# GCIT_1_0.net
KiCad netlist of a schematic drawn in Altium Designer
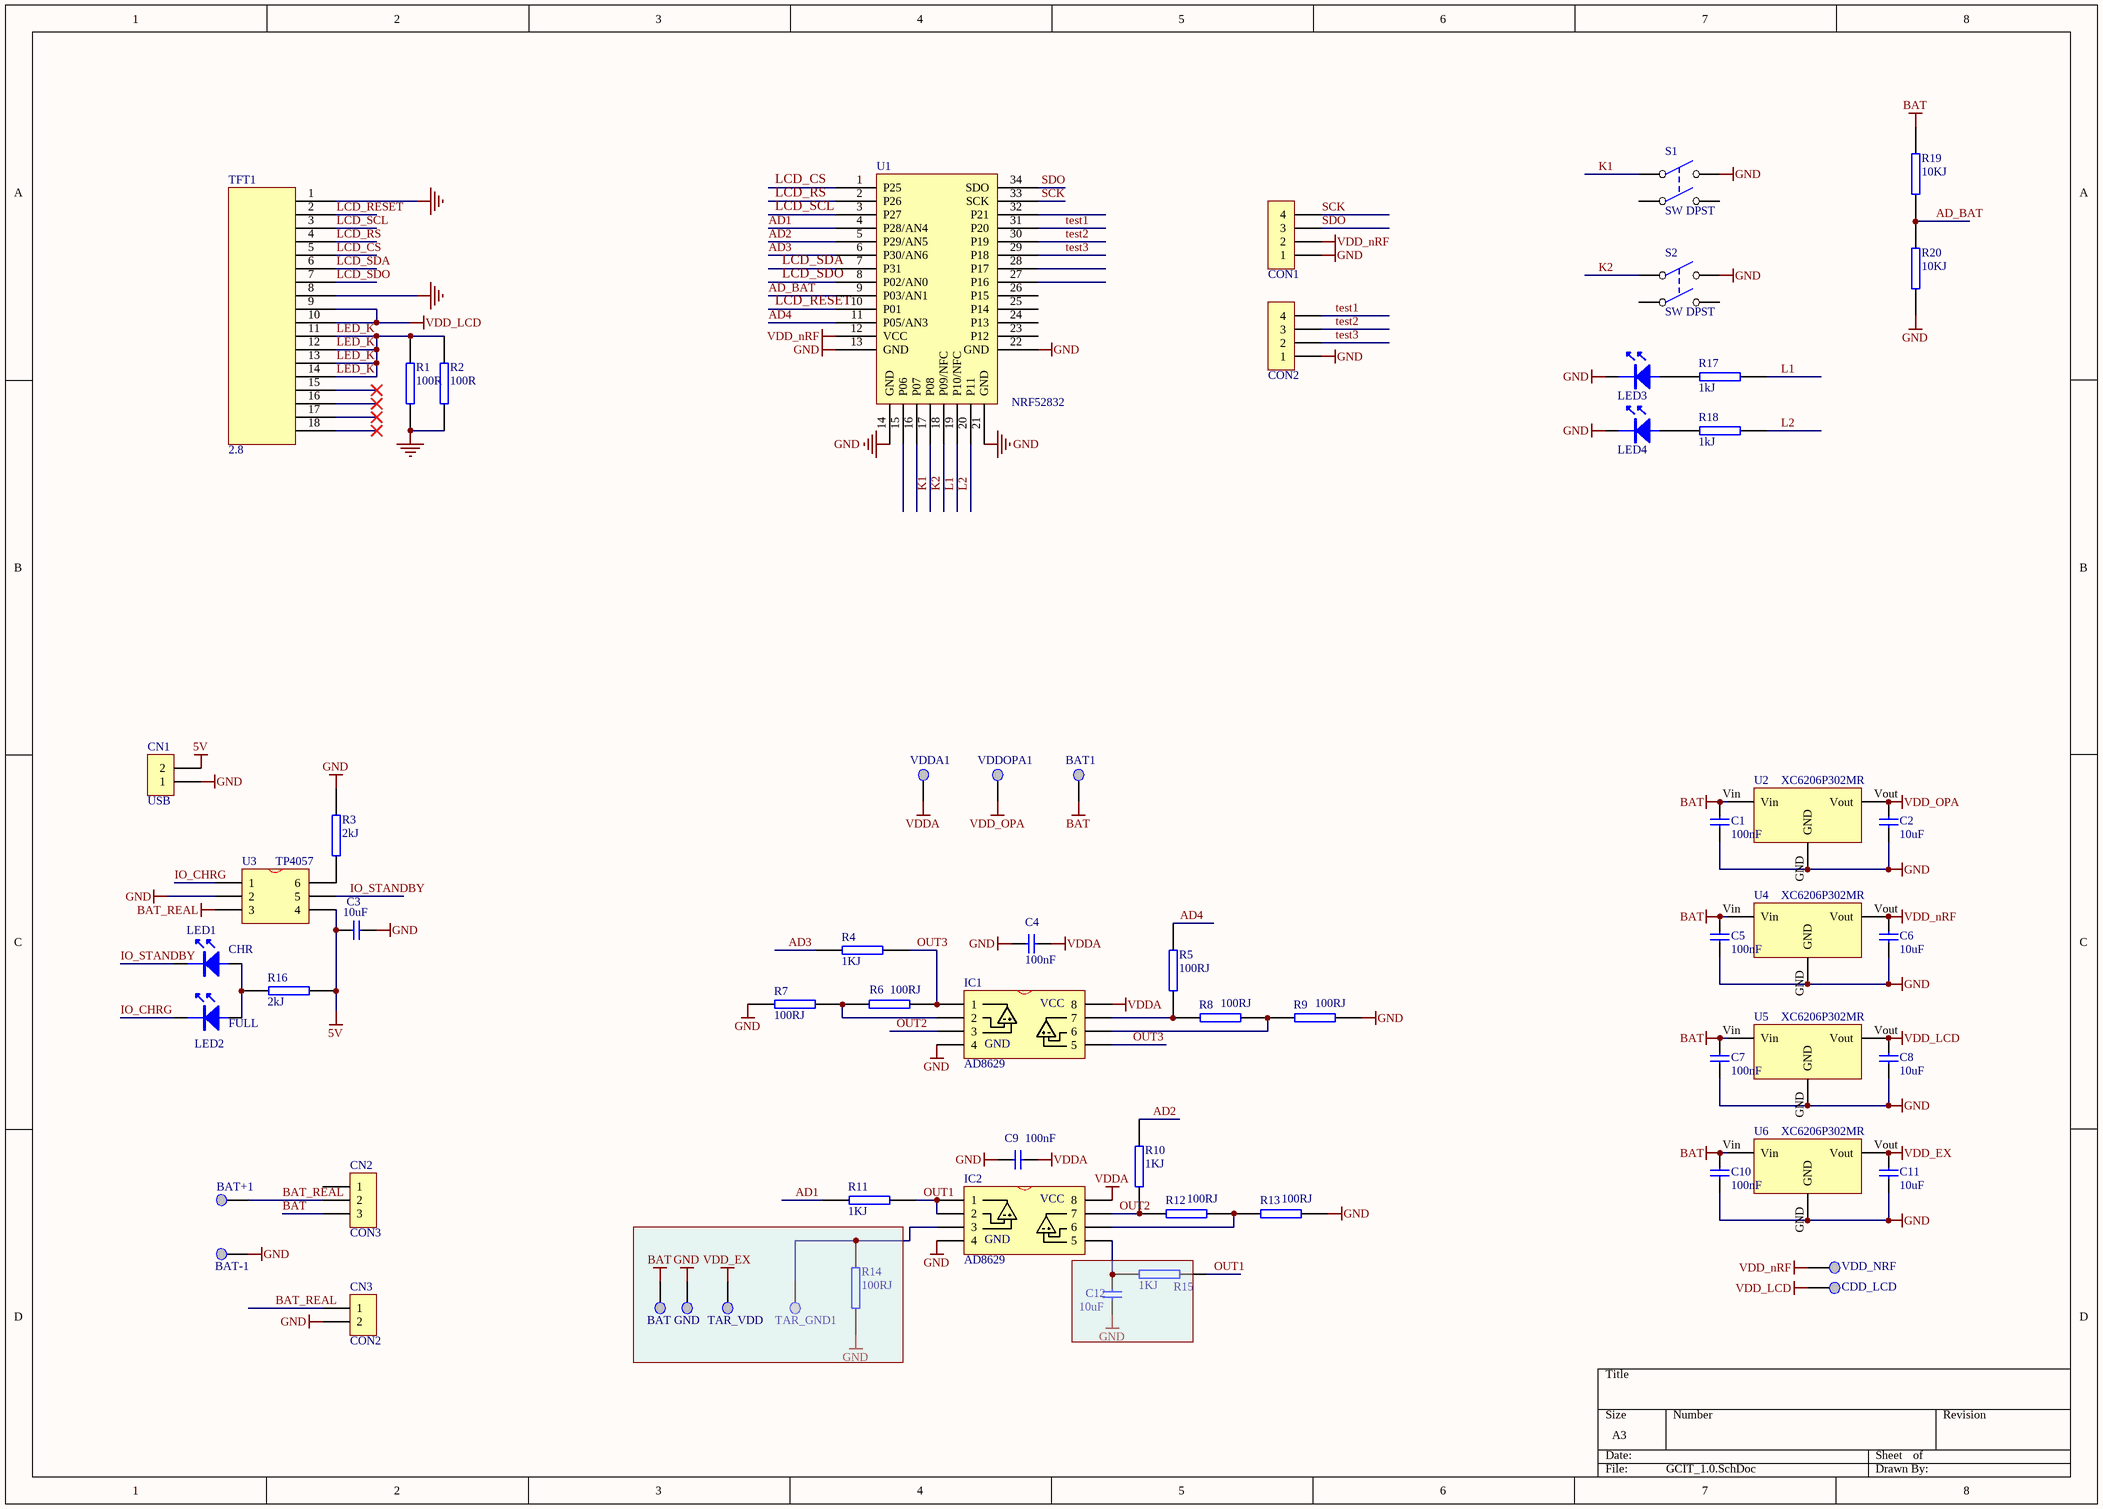
[diagram p0: GCIT_1.0.SchDoc]

(export (version "E")
  (design (tool "Eeschema 10.0.6"))
  (components
    (comp (ref "BAT") (value "~") (footprint "BAT_PAD") (libsource (lib "LZMSCH库") (part "PAD")))
    (comp (ref "BAT+1") (value "~") (footprint "BAT_PAD") (libsource (lib "LZMSCH库") (part "PAD")))
    (comp (ref "BAT-1") (value "~") (footprint "BAT_PAD") (libsource (lib "LZMSCH库") (part "PAD")))
    (comp (ref "BAT1") (value "~") (footprint "BAT_PAD") (libsource (lib "LZMSCH库") (part "PAD")))
    (comp (ref "C1")
      (value "100nF")
      (footprint "0603C")
      (description "Capacitor, X7R, ?0%")
      (fields (field (name "PART NUMBER") "C0402-47n") (field (name "PUBLISHER") "Nordic Semiconductor"))
      (libsource (lib "Nordic Passive DB") (part "CAP"))
    )
    (comp (ref "C2")
      (value "10uF")
      (footprint "0603C")
      (description "Capacitor, X7R, ?0%")
      (fields (field (name "PART NUMBER") "C0402-47n") (field (name "PUBLISHER") "Nordic Semiconductor"))
      (libsource (lib "Nordic Passive DB") (part "CAP"))
    )
    (comp (ref "C3")
      (value "10uF")
      (footprint "0603C")
      (description "Capacitor, X7R, ?0%")
      (fields (field (name "PART NUMBER") "C0402-47n") (field (name "PUBLISHER") "Nordic Semiconductor"))
      (libsource (lib "Nordic Passive DB") (part "CAP"))
    )
    (comp (ref "C4")
      (value "100nF")
      (footprint "0603C")
      (description "Capacitor, X7R, ?0%")
      (fields (field (name "PART NUMBER") "C0402-47n") (field (name "PUBLISHER") "Nordic Semiconductor"))
      (libsource (lib "Nordic Passive DB") (part "CAP"))
    )
    (comp (ref "C5")
      (value "100nF")
      (footprint "0603C")
      (description "Capacitor, X7R, ?0%")
      (fields (field (name "PART NUMBER") "C0402-47n") (field (name "PUBLISHER") "Nordic Semiconductor"))
      (libsource (lib "Nordic Passive DB") (part "CAP"))
    )
    (comp (ref "C6")
      (value "10uF")
      (footprint "0603C")
      (description "Capacitor, X7R, ?0%")
      (fields (field (name "PART NUMBER") "C0402-47n") (field (name "PUBLISHER") "Nordic Semiconductor"))
      (libsource (lib "Nordic Passive DB") (part "CAP"))
    )
    (comp (ref "C7")
      (value "100nF")
      (footprint "0603C")
      (description "Capacitor, X7R, ?0%")
      (fields (field (name "PART NUMBER") "C0402-47n") (field (name "PUBLISHER") "Nordic Semiconductor"))
      (libsource (lib "Nordic Passive DB") (part "CAP"))
    )
    (comp (ref "C8")
      (value "10uF")
      (footprint "0603C")
      (description "Capacitor, X7R, ?0%")
      (fields (field (name "PART NUMBER") "C0402-47n") (field (name "PUBLISHER") "Nordic Semiconductor"))
      (libsource (lib "Nordic Passive DB") (part "CAP"))
    )
    (comp (ref "C9")
      (value "100nF")
      (footprint "0603C")
      (description "Capacitor, X7R, ?0%")
      (fields (field (name "PART NUMBER") "C0402-47n") (field (name "PUBLISHER") "Nordic Semiconductor"))
      (libsource (lib "Nordic Passive DB") (part "CAP"))
    )
    (comp (ref "C10")
      (value "100nF")
      (footprint "0603C")
      (description "Capacitor, X7R, ?0%")
      (fields (field (name "PART NUMBER") "C0402-47n") (field (name "PUBLISHER") "Nordic Semiconductor"))
      (libsource (lib "Nordic Passive DB") (part "CAP"))
    )
    (comp (ref "C11")
      (value "10uF")
      (footprint "0603C")
      (description "Capacitor, X7R, ?0%")
      (fields (field (name "PART NUMBER") "C0402-47n") (field (name "PUBLISHER") "Nordic Semiconductor"))
      (libsource (lib "Nordic Passive DB") (part "CAP"))
    )
    (comp (ref "C12")
      (value "10uF")
      (footprint "0603C")
      (description "Capacitor, X7R, ?0%")
      (fields (field (name "PART NUMBER") "C0402-47n") (field (name "PUBLISHER") "Nordic Semiconductor"))
      (libsource (lib "Nordic Passive DB") (part "CAP"))
    )
    (comp (ref "CDD_LCD") (value "~") (footprint "BAT_PAD") (libsource (lib "LZMSCH库") (part "PAD")))
    (comp (ref "CN1")
      (value "USB")
      (footprint "USB")
      (description "Connector")
      (libsource (lib "") (part "CON2_1"))
    )
    (comp (ref "CN2")
      (value "CON3")
      (footprint "MSK-12C01-07")
      (description "Connector")
      (libsource (lib "LZMSCH库") (part "CON3"))
    )
    (comp (ref "CN3")
      (value "CON2")
      (footprint "SIP-2P")
      (description "Connector")
      (libsource (lib "LZMSCH库") (part "CON2"))
    )
    (comp (ref "CON1")
      (value "CON4")
      (footprint "SIP-4P")
      (description "Connector")
      (libsource (lib "LZMSCH库") (part "CON4"))
    )
    (comp (ref "CON2")
      (value "CON4")
      (footprint "SIP-4P")
      (description "Connector")
      (libsource (lib "LZMSCH库") (part "CON4"))
    )
    (comp (ref "GND") (value "~") (footprint "BAT_PAD") (libsource (lib "LZMSCH库") (part "PAD")))
    (comp (ref "IC1") (value "AD8629") (footprint "SO-8") (libsource (lib "") (part "LM358_1")))
    (comp (ref "IC2") (value "AD8629") (footprint "SO-8") (libsource (lib "LZMSCH库") (part "LM358")))
    (comp (ref "LED1") (value "CHR") (footprint "0603LED") (libsource (lib "LZMSCH库") (part "LED")))
    (comp (ref "LED2") (value "FULL") (footprint "0603LED") (libsource (lib "LZMSCH库") (part "LED")))
    (comp (ref "LED3") (value "CHR") (footprint "0603LED") (libsource (lib "LZMSCH库") (part "LED")))
    (comp (ref "LED4") (value "[]") (footprint "0603LED") (libsource (lib "LZMSCH库") (part "LED")))
    (comp (ref "R1") (value "100R") (footprint "0603R") (libsource (lib "*") (part "RES2")))
    (comp (ref "R2") (value "100R") (footprint "0603R") (libsource (lib "*") (part "RES2")))
    (comp (ref "R3") (value "2kJ") (footprint "0603R") (libsource (lib "*") (part "RES2")))
    (comp (ref "R4") (value "1KJ") (footprint "0603R") (libsource (lib "*") (part "RES2")))
    (comp (ref "R5") (value "100RJ") (footprint "0603R") (libsource (lib "*") (part "RES2")))
    (comp (ref "R6") (value "100RJ") (footprint "0603R") (libsource (lib "*") (part "RES2")))
    (comp (ref "R7") (value "100RJ") (footprint "0603R") (libsource (lib "*") (part "RES2")))
    (comp (ref "R8") (value "100RJ") (footprint "0603R") (libsource (lib "*") (part "RES2")))
    (comp (ref "R9") (value "100RJ") (footprint "0603R") (libsource (lib "*") (part "RES2")))
    (comp (ref "R10") (value "1KJ") (footprint "0603R") (libsource (lib "*") (part "RES2")))
    (comp (ref "R11") (value "1KJ") (footprint "0603R") (libsource (lib "*") (part "RES2")))
    (comp (ref "R12") (value "100RJ") (footprint "0603R") (libsource (lib "*") (part "RES2")))
    (comp (ref "R13") (value "100RJ") (footprint "0603R") (libsource (lib "*") (part "RES2")))
    (comp (ref "R14") (value "100RJ") (footprint "0603R") (libsource (lib "*") (part "RES2")))
    (comp (ref "R15") (value "1KJ") (footprint "0603R") (libsource (lib "*") (part "RES2")))
    (comp (ref "R16") (value "2kJ") (footprint "0603R") (libsource (lib "*") (part "RES2")))
    (comp (ref "R17") (value "1kJ") (footprint "0603R") (libsource (lib "*") (part "RES2")))
    (comp (ref "R18") (value "1kJ") (footprint "0603R") (libsource (lib "*") (part "RES2")))
    (comp (ref "R19") (value "10KJ") (footprint "0603R") (libsource (lib "*") (part "RES2")))
    (comp (ref "R20") (value "10KJ") (footprint "0603R") (libsource (lib "*") (part "RES2")))
    (comp (ref "S1") (value "SW DPST") (footprint "key4x4") (libsource (lib "LZMSCH库") (part "SW DPST")))
    (comp (ref "S2") (value "SW DPST") (footprint "key4x4") (libsource (lib "LZMSCH库") (part "SW DPST")))
    (comp (ref "TAR_GND1") (value "~") (footprint "DEBUG_PAD") (libsource (lib "LZMSCH库") (part "PAD")))
    (comp (ref "TAR_VDD") (value "~") (footprint "BAT_PAD") (libsource (lib "LZMSCH库") (part "PAD")))
    (comp (ref "TFT1") (value "2.8") (footprint "TFT2.8-ZHA") (libsource (lib "*") (part "18P")))
    (comp (ref "U1")
      (value "NRF52832")
      (footprint "NRF52832_MODEL")
      (libsource (lib "LZMSCH库") (part "NRF52832"))
    )
    (comp (ref "U2")
      (value "XC6206P302MR")
      (footprint "SOT-23-S-LDO")
      (libsource (lib "LZMSCH库") (part "7805"))
    )
    (comp (ref "U3") (value "TP4057") (footprint "SOT23-6-SMALL") (libsource (lib "LZMSCH库") (part "DIP6")))
    (comp (ref "U4")
      (value "XC6206P302MR")
      (footprint "SOT-23-S-LDO")
      (libsource (lib "LZMSCH库") (part "7805"))
    )
    (comp (ref "U5")
      (value "XC6206P302MR")
      (footprint "SOT-23-S-LDO")
      (libsource (lib "LZMSCH库") (part "7805"))
    )
    (comp (ref "U6")
      (value "XC6206P302MR")
      (footprint "SOT-23-S-LDO")
      (libsource (lib "LZMSCH库") (part "7805"))
    )
    (comp (ref "VDDA1") (value "~") (footprint "BAT_PAD") (libsource (lib "LZMSCH库") (part "PAD")))
    (comp (ref "VDDOPA1") (value "~") (footprint "BAT_PAD") (libsource (lib "LZMSCH库") (part "PAD")))
    (comp (ref "VDD_NRF") (value "~") (footprint "BAT_PAD") (libsource (lib "LZMSCH库") (part "PAD")))
  )
  (nets
    (net (code "1") (name "/AD1") (class "Default")
      (node (ref "R11") (pin "2") (pinfunction "2_2") (pintype "passive"))
      (node (ref "U1") (pin "4") (pinfunction "P28/AN4_4") (pintype "passive"))
    )
    (net (code "2") (name "/AD2") (class "Default")
      (node (ref "R10") (pin "2") (pinfunction "2_2") (pintype "passive"))
      (node (ref "U1") (pin "5") (pinfunction "P29/AN5_5") (pintype "passive"))
    )
    (net (code "3") (name "/AD3") (class "Default")
      (node (ref "R4") (pin "2") (pinfunction "2_2") (pintype "passive"))
      (node (ref "U1") (pin "6") (pinfunction "P30/AN6_6") (pintype "passive"))
    )
    (net (code "4") (name "/AD4") (class "Default")
      (node (ref "R5") (pin "2") (pinfunction "2_2") (pintype "passive"))
      (node (ref "U1") (pin "11") (pinfunction "P05/AN3_11") (pintype "passive"))
    )
    (net (code "5") (name "/AD_BAT") (class "Default")
      (node (ref "R19") (pin "1") (pinfunction "1_1") (pintype "passive"))
      (node (ref "R20") (pin "2") (pinfunction "2_2") (pintype "passive"))
      (node (ref "U1") (pin "9") (pinfunction "P03/AN1_9") (pintype "passive"))
    )
    (net (code "6") (name "/IO_CHRG") (class "Default")
      (node (ref "LED2") (pin "K") (pinfunction "2_K") (pintype "passive"))
      (node (ref "U3") (pin "1") (pinfunction "1_1") (pintype "passive"))
    )
    (net (code "7") (name "/IO_STANDBY") (class "Default")
      (node (ref "LED1") (pin "K") (pinfunction "2_K") (pintype "passive"))
      (node (ref "U3") (pin "5") (pinfunction "5_5") (pintype "passive"))
    )
    (net (code "8") (name "/K1") (class "Default")
      (node (ref "S1") (pin "1") (pinfunction "COMMON1_1") (pintype "passive"))
      (node (ref "U1") (pin "17") (pinfunction "P08_17") (pintype "passive"))
    )
    (net (code "9") (name "/K2") (class "Default")
      (node (ref "S2") (pin "1") (pinfunction "COMMON1_1") (pintype "passive"))
      (node (ref "U1") (pin "18") (pinfunction "P09/NFC_18") (pintype "passive"))
    )
    (net (code "10") (name "/L1") (class "Default")
      (node (ref "R17") (pin "1") (pinfunction "1_1") (pintype "passive"))
      (node (ref "U1") (pin "19") (pinfunction "P10/NFC_19") (pintype "passive"))
    )
    (net (code "11") (name "/L2") (class "Default")
      (node (ref "R18") (pin "1") (pinfunction "1_1") (pintype "passive"))
      (node (ref "U1") (pin "20") (pinfunction "P11_20") (pintype "passive"))
    )
    (net (code "12") (name "/LCD_CS") (class "Default")
      (node (ref "TFT1") (pin "5") (pintype "passive"))
      (node (ref "U1") (pin "1") (pinfunction "P25_1") (pintype "passive"))
    )
    (net (code "13") (name "/LCD_RESET") (class "Default")
      (node (ref "TFT1") (pin "2") (pintype "passive"))
      (node (ref "U1") (pin "10") (pinfunction "P01_10") (pintype "passive"))
    )
    (net (code "14") (name "/LCD_RS") (class "Default")
      (node (ref "TFT1") (pin "4") (pintype "passive"))
      (node (ref "U1") (pin "2") (pinfunction "P26_2") (pintype "passive"))
    )
    (net (code "15") (name "/LCD_SCL") (class "Default")
      (node (ref "TFT1") (pin "3") (pintype "passive"))
      (node (ref "U1") (pin "3") (pinfunction "P27_3") (pintype "passive"))
    )
    (net (code "16") (name "/LCD_SDA") (class "Default")
      (node (ref "TFT1") (pin "6") (pintype "passive"))
      (node (ref "U1") (pin "7") (pinfunction "P31_7") (pintype "passive"))
    )
    (net (code "17") (name "/LCD_SDO") (class "Default")
      (node (ref "TFT1") (pin "7") (pintype "passive"))
      (node (ref "U1") (pin "8") (pinfunction "P02/AN0_8") (pintype "passive"))
    )
    (net (code "18") (name "/LED_K") (class "Default")
      (node (ref "R1") (pin "2") (pinfunction "2_2") (pintype "passive"))
      (node (ref "R2") (pin "2") (pinfunction "2_2") (pintype "passive"))
      (node (ref "TFT1") (pin "11") (pintype "passive"))
      (node (ref "TFT1") (pin "12") (pintype "passive"))
      (node (ref "TFT1") (pin "13") (pintype "passive"))
      (node (ref "TFT1") (pin "14") (pintype "passive"))
    )
    (net (code "19") (name "/OUT1") (class "Default")
      (node (ref "IC2") (pin "1") (pinfunction "1_1") (pintype "passive"))
      (node (ref "IC2") (pin "2") (pinfunction "2_2") (pintype "passive"))
      (node (ref "R11") (pin "1") (pinfunction "1_1") (pintype "passive"))
      (node (ref "R15") (pin "1") (pinfunction "1_1") (pintype "passive"))
    )
    (net (code "20") (name "/OUT2") (class "Default")
      (node (ref "IC1") (pin "3") (pinfunction "3_3") (pintype "passive"))
      (node (ref "IC2") (pin "7") (pinfunction "7_7") (pintype "passive"))
      (node (ref "R10") (pin "1") (pinfunction "1_1") (pintype "passive"))
      (node (ref "R12") (pin "2") (pinfunction "2_2") (pintype "passive"))
    )
    (net (code "21") (name "/OUT3") (class "Default")
      (node (ref "IC1") (pin "1") (pinfunction "1_1") (pintype "passive"))
      (node (ref "IC1") (pin "5") (pinfunction "5_5") (pintype "passive"))
      (node (ref "R4") (pin "1") (pinfunction "1_1") (pintype "passive"))
      (node (ref "R6") (pin "2") (pinfunction "2_2") (pintype "passive"))
    )
    (net (code "22") (name "/SCK") (class "Default")
      (node (ref "CON1") (pin "4") (pinfunction "4_4") (pintype "passive"))
      (node (ref "U1") (pin "33") (pinfunction "SCK_33") (pintype "passive"))
    )
    (net (code "23") (name "/SDO") (class "Default")
      (node (ref "CON1") (pin "3") (pinfunction "3_3") (pintype "passive"))
      (node (ref "U1") (pin "34") (pinfunction "SDO_34") (pintype "passive"))
    )
    (net (code "24") (name "/test1") (class "Default")
      (node (ref "CON2") (pin "4") (pinfunction "4_4") (pintype "passive"))
      (node (ref "U1") (pin "31") (pinfunction "P20_31") (pintype "passive"))
    )
    (net (code "25") (name "/test2") (class "Default")
      (node (ref "CON2") (pin "3") (pinfunction "3_3") (pintype "passive"))
      (node (ref "U1") (pin "30") (pinfunction "P19_30") (pintype "passive"))
    )
    (net (code "26") (name "/test3") (class "Default")
      (node (ref "CON2") (pin "2") (pinfunction "2_2") (pintype "passive"))
      (node (ref "U1") (pin "29") (pinfunction "P18_29") (pintype "passive"))
    )
    (net (code "27") (name "5V") (class "Default")
      (node (ref "C3") (pin "1") (pinfunction "1_1") (pintype "passive"))
      (node (ref "CN1") (pin "2") (pinfunction "2_2") (pintype "passive"))
      (node (ref "R16") (pin "1") (pinfunction "1_1") (pintype "passive"))
      (node (ref "U3") (pin "4") (pinfunction "4_4") (pintype "passive"))
    )
    (net (code "28") (name "BAT") (class "Default")
      (node (ref "BAT") (pin "1") (pinfunction "1_1") (pintype "passive"))
      (node (ref "BAT1") (pin "1") (pinfunction "1_1") (pintype "passive"))
      (node (ref "C1") (pin "2") (pinfunction "2_2") (pintype "passive"))
      (node (ref "C10") (pin "2") (pinfunction "2_2") (pintype "passive"))
      (node (ref "C5") (pin "2") (pinfunction "2_2") (pintype "passive"))
      (node (ref "C7") (pin "2") (pinfunction "2_2") (pintype "passive"))
      (node (ref "CN2") (pin "3") (pinfunction "3_3") (pintype "passive"))
      (node (ref "R19") (pin "2") (pinfunction "2_2") (pintype "passive"))
      (node (ref "U2") (pin "Vin") (pinfunction "Vin_Vin") (pintype "passive"))
      (node (ref "U4") (pin "Vin") (pinfunction "Vin_Vin") (pintype "passive"))
      (node (ref "U5") (pin "Vin") (pinfunction "Vin_Vin") (pintype "passive"))
      (node (ref "U6") (pin "Vin") (pinfunction "Vin_Vin") (pintype "passive"))
    )
    (net (code "29") (name "BAT_REAL") (class "Default")
      (node (ref "BAT+1") (pin "1") (pinfunction "1_1") (pintype "passive"))
      (node (ref "CN2") (pin "2") (pinfunction "2_2") (pintype "passive"))
      (node (ref "CN3") (pin "1") (pinfunction "1_1") (pintype "passive"))
      (node (ref "U3") (pin "3") (pinfunction "3_3") (pintype "passive"))
    )
    (net (code "30") (name "GND") (class "Default")
      (node (ref "BAT-1") (pin "1") (pinfunction "1_1") (pintype "passive"))
      (node (ref "C1") (pin "1") (pinfunction "1_1") (pintype "passive"))
      (node (ref "C10") (pin "1") (pinfunction "1_1") (pintype "passive"))
      (node (ref "C11") (pin "1") (pinfunction "1_1") (pintype "passive"))
      (node (ref "C12") (pin "1") (pinfunction "1_1") (pintype "passive"))
      (node (ref "C2") (pin "1") (pinfunction "1_1") (pintype "passive"))
      (node (ref "C3") (pin "2") (pinfunction "2_2") (pintype "passive"))
      (node (ref "C4") (pin "1") (pinfunction "1_1") (pintype "passive"))
      (node (ref "C5") (pin "1") (pinfunction "1_1") (pintype "passive"))
      (node (ref "C6") (pin "1") (pinfunction "1_1") (pintype "passive"))
      (node (ref "C7") (pin "1") (pinfunction "1_1") (pintype "passive"))
      (node (ref "C8") (pin "1") (pinfunction "1_1") (pintype "passive"))
      (node (ref "C9") (pin "1") (pinfunction "1_1") (pintype "passive"))
      (node (ref "CN1") (pin "1") (pinfunction "1_1") (pintype "passive"))
      (node (ref "CN3") (pin "2") (pinfunction "2_2") (pintype "passive"))
      (node (ref "CON1") (pin "1") (pinfunction "1_1") (pintype "passive"))
      (node (ref "CON2") (pin "1") (pinfunction "1_1") (pintype "passive"))
      (node (ref "GND") (pin "1") (pinfunction "1_1") (pintype "passive"))
      (node (ref "IC1") (pin "4") (pinfunction "4_4") (pintype "passive"))
      (node (ref "IC2") (pin "4") (pinfunction "4_4") (pintype "passive"))
      (node (ref "LED3") (pin "K") (pinfunction "2_K") (pintype "passive"))
      (node (ref "LED4") (pin "K") (pinfunction "2_K") (pintype "passive"))
      (node (ref "R1") (pin "1") (pinfunction "1_1") (pintype "passive"))
      (node (ref "R13") (pin "1") (pinfunction "1_1") (pintype "passive"))
      (node (ref "R14") (pin "2") (pinfunction "2_2") (pintype "passive"))
      (node (ref "R2") (pin "1") (pinfunction "1_1") (pintype "passive"))
      (node (ref "R20") (pin "1") (pinfunction "1_1") (pintype "passive"))
      (node (ref "R3") (pin "2") (pinfunction "2_2") (pintype "passive"))
      (node (ref "R7") (pin "1") (pinfunction "1_1") (pintype "passive"))
      (node (ref "R9") (pin "1") (pinfunction "1_1") (pintype "passive"))
      (node (ref "S1") (pin "2") (pinfunction "NO1_2") (pintype "passive"))
      (node (ref "S2") (pin "2") (pinfunction "NO1_2") (pintype "passive"))
      (node (ref "TFT1") (pin "1") (pintype "passive"))
      (node (ref "TFT1") (pin "8") (pintype "passive"))
      (node (ref "U1") (pin "13") (pinfunction "GND_13") (pintype "passive"))
      (node (ref "U1") (pin "14") (pinfunction "GND_14") (pintype "passive"))
      (node (ref "U1") (pin "21") (pinfunction "GND_21") (pintype "passive"))
      (node (ref "U1") (pin "22") (pinfunction "GND_22") (pintype "passive"))
      (node (ref "U2") (pin "GND") (pinfunction "GND_GND") (pintype "passive"))
      (node (ref "U3") (pin "2") (pinfunction "2_2") (pintype "passive"))
      (node (ref "U4") (pin "GND") (pinfunction "GND_GND") (pintype "passive"))
      (node (ref "U5") (pin "GND") (pinfunction "GND_GND") (pintype "passive"))
      (node (ref "U6") (pin "GND") (pinfunction "GND_GND") (pintype "passive"))
    )
    (net (code "31") (name "Net-(C12-Pad2)") (class "Default")
      (node (ref "C12") (pin "2") (pinfunction "2_2") (pintype "passive"))
      (node (ref "IC2") (pin "5") (pinfunction "5_5") (pintype "passive"))
      (node (ref "R15") (pin "2") (pinfunction "2_2") (pintype "passive"))
    )
    (net (code "32") (name "Net-(IC1-Pad2)") (class "Default")
      (node (ref "IC1") (pin "2") (pinfunction "2_2") (pintype "passive"))
      (node (ref "R6") (pin "1") (pinfunction "1_1") (pintype "passive"))
      (node (ref "R7") (pin "2") (pinfunction "2_2") (pintype "passive"))
    )
    (net (code "33") (name "Net-(IC1-Pad6)") (class "Default")
      (node (ref "IC1") (pin "6") (pinfunction "6_6") (pintype "passive"))
      (node (ref "R8") (pin "1") (pinfunction "1_1") (pintype "passive"))
      (node (ref "R9") (pin "2") (pinfunction "2_2") (pintype "passive"))
    )
    (net (code "34") (name "Net-(IC1-Pad7)") (class "Default")
      (node (ref "IC1") (pin "7") (pinfunction "7_7") (pintype "passive"))
      (node (ref "R5") (pin "1") (pinfunction "1_1") (pintype "passive"))
      (node (ref "R8") (pin "2") (pinfunction "2_2") (pintype "passive"))
    )
    (net (code "35") (name "Net-(IC2-Pad3)") (class "Default")
      (node (ref "IC2") (pin "3") (pinfunction "3_3") (pintype "passive"))
      (node (ref "R14") (pin "1") (pinfunction "1_1") (pintype "passive"))
      (node (ref "TAR_GND1") (pin "1") (pinfunction "1_1") (pintype "passive"))
    )
    (net (code "36") (name "Net-(IC2-Pad6)") (class "Default")
      (node (ref "IC2") (pin "6") (pinfunction "6_6") (pintype "passive"))
      (node (ref "R12") (pin "1") (pinfunction "1_1") (pintype "passive"))
      (node (ref "R13") (pin "2") (pinfunction "2_2") (pintype "passive"))
    )
    (net (code "37") (name "Net-(LED1-1)") (class "Default")
      (node (ref "LED1") (pin "A") (pinfunction "1_A") (pintype "passive"))
      (node (ref "LED2") (pin "A") (pinfunction "1_A") (pintype "passive"))
      (node (ref "R16") (pin "2") (pinfunction "2_2") (pintype "passive"))
    )
    (net (code "38") (name "Net-(LED3-1)") (class "Default")
      (node (ref "LED3") (pin "A") (pinfunction "1_A") (pintype "passive"))
      (node (ref "R17") (pin "2") (pinfunction "2_2") (pintype "passive"))
    )
    (net (code "39") (name "Net-(LED4-1)") (class "Default")
      (node (ref "LED4") (pin "A") (pinfunction "1_A") (pintype "passive"))
      (node (ref "R18") (pin "2") (pinfunction "2_2") (pintype "passive"))
    )
    (net (code "40") (name "Net-(R3-Pad1)") (class "Default")
      (node (ref "R3") (pin "1") (pinfunction "1_1") (pintype "passive"))
      (node (ref "U3") (pin "6") (pinfunction "6_6") (pintype "passive"))
    )
    (net (code "41") (name "VDDA") (class "Default")
      (node (ref "C4") (pin "2") (pinfunction "2_2") (pintype "passive"))
      (node (ref "C9") (pin "2") (pinfunction "2_2") (pintype "passive"))
      (node (ref "IC1") (pin "8") (pinfunction "8_8") (pintype "passive"))
      (node (ref "IC2") (pin "8") (pinfunction "8_8") (pintype "passive"))
      (node (ref "VDDA1") (pin "1") (pinfunction "1_1") (pintype "passive"))
    )
    (net (code "42") (name "VDD_EX") (class "Default")
      (node (ref "C11") (pin "2") (pinfunction "2_2") (pintype "passive"))
      (node (ref "TAR_VDD") (pin "1") (pinfunction "1_1") (pintype "passive"))
      (node (ref "U6") (pin "Vout") (pinfunction "Vout_Vout") (pintype "passive"))
    )
    (net (code "43") (name "VDD_LCD") (class "Default")
      (node (ref "C8") (pin "2") (pinfunction "2_2") (pintype "passive"))
      (node (ref "CDD_LCD") (pin "1") (pinfunction "1_1") (pintype "passive"))
      (node (ref "TFT1") (pin "10") (pintype "passive"))
      (node (ref "TFT1") (pin "9") (pintype "passive"))
      (node (ref "U5") (pin "Vout") (pinfunction "Vout_Vout") (pintype "passive"))
    )
    (net (code "44") (name "VDD_OPA") (class "Default")
      (node (ref "C2") (pin "2") (pinfunction "2_2") (pintype "passive"))
      (node (ref "U2") (pin "Vout") (pinfunction "Vout_Vout") (pintype "passive"))
      (node (ref "VDDOPA1") (pin "1") (pinfunction "1_1") (pintype "passive"))
    )
    (net (code "45") (name "VDD_nRF") (class "Default")
      (node (ref "C6") (pin "2") (pinfunction "2_2") (pintype "passive"))
      (node (ref "CON1") (pin "2") (pinfunction "2_2") (pintype "passive"))
      (node (ref "U1") (pin "12") (pinfunction "VCC_12") (pintype "passive"))
      (node (ref "U4") (pin "Vout") (pinfunction "Vout_Vout") (pintype "passive"))
      (node (ref "VDD_NRF") (pin "1") (pinfunction "1_1") (pintype "passive"))
    )
    (net (code "46") (name "unconnected-(CN2-Pad1)") (class "Default")
      (node (ref "CN2") (pin "1") (pinfunction "1_1") (pintype "passive"))
    )
    (net (code "47") (name "unconnected-(S1-COMMON2-Pad3)") (class "Default")
      (node (ref "S1") (pin "3") (pinfunction "COMMON2_3") (pintype "passive"))
    )
    (net (code "48") (name "unconnected-(S1-NO2-Pad4)") (class "Default")
      (node (ref "S1") (pin "4") (pinfunction "NO2_4") (pintype "passive"))
    )
    (net (code "49") (name "unconnected-(S2-COMMON2-Pad3)") (class "Default")
      (node (ref "S2") (pin "3") (pinfunction "COMMON2_3") (pintype "passive"))
    )
    (net (code "50") (name "unconnected-(S2-NO2-Pad4)") (class "Default")
      (node (ref "S2") (pin "4") (pinfunction "NO2_4") (pintype "passive"))
    )
    (net (code "51") (name "unconnected-(TFT1-Pad15)") (class "Default")
      (node (ref "TFT1") (pin "15") (pintype "passive+no_connect"))
    )
    (net (code "52") (name "unconnected-(TFT1-Pad16)") (class "Default")
      (node (ref "TFT1") (pin "16") (pintype "passive+no_connect"))
    )
    (net (code "53") (name "unconnected-(TFT1-Pad17)") (class "Default")
      (node (ref "TFT1") (pin "17") (pintype "passive+no_connect"))
    )
    (net (code "54") (name "unconnected-(TFT1-Pad18)") (class "Default")
      (node (ref "TFT1") (pin "18") (pintype "passive+no_connect"))
    )
    (net (code "55") (name "unconnected-(U1-P06-Pad15)") (class "Default")
      (node (ref "U1") (pin "15") (pinfunction "P06_15") (pintype "passive"))
    )
    (net (code "56") (name "unconnected-(U1-P07-Pad16)") (class "Default")
      (node (ref "U1") (pin "16") (pinfunction "P07_16") (pintype "passive"))
    )
    (net (code "57") (name "unconnected-(U1-P12-Pad23)") (class "Default")
      (node (ref "U1") (pin "23") (pinfunction "P12_23") (pintype "passive"))
    )
    (net (code "58") (name "unconnected-(U1-P13-Pad24)") (class "Default")
      (node (ref "U1") (pin "24") (pinfunction "P13_24") (pintype "passive"))
    )
    (net (code "59") (name "unconnected-(U1-P14-Pad25)") (class "Default")
      (node (ref "U1") (pin "25") (pinfunction "P14_25") (pintype "passive"))
    )
    (net (code "60") (name "unconnected-(U1-P15-Pad26)") (class "Default")
      (node (ref "U1") (pin "26") (pinfunction "P15_26") (pintype "passive"))
    )
    (net (code "61") (name "unconnected-(U1-P16-Pad27)") (class "Default")
      (node (ref "U1") (pin "27") (pinfunction "P16_27") (pintype "passive"))
    )
    (net (code "62") (name "unconnected-(U1-P17-Pad28)") (class "Default")
      (node (ref "U1") (pin "28") (pinfunction "P17_28") (pintype "passive"))
    )
    (net (code "63") (name "unconnected-(U1-P21-Pad32)") (class "Default")
      (node (ref "U1") (pin "32") (pinfunction "P21_32") (pintype "passive"))
    )
  )
)
